# subckt_SMPS_EMI_filter.net
KiCad netlist of a schematic drawn in Altium Designer
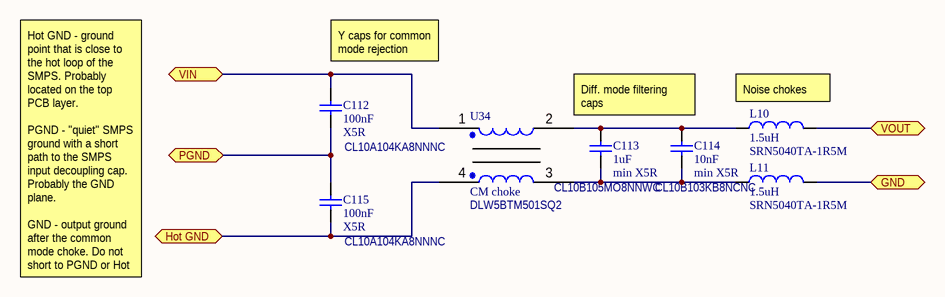
[diagram p0: subckt_SMPS_EMI_filter.SchDoc]

(export (version "E")
  (design (tool "Eeschema 10.0.6"))
  (components
    (comp (ref "C112")
      (value "100nF")
      (footprint "CAP0603")
      (description "Capacitor")
      (fields (field (name "DIELECTRIC") "X5R") (field (name "MODEL") "CL10A104KA8NNNC"))
      (libsource (lib "lib_basic") (part "Capacitor"))
    )
    (comp (ref "C113")
      (value "1uF")
      (footprint "CAP0603")
      (description "Capacitor")
      (fields (field (name "DIELECTRIC") "min X5R") (field (name "MODEL") "CL10B105MO8NNWC"))
      (libsource (lib "lib_basic") (part "Capacitor"))
    )
    (comp (ref "C114")
      (value "10nF")
      (footprint "CAP0603")
      (description "Capacitor")
      (fields (field (name "DIELECTRIC") "min X5R") (field (name "MODEL") "CL10B103KB8NCNC"))
      (libsource (lib "lib_basic") (part "Capacitor"))
    )
    (comp (ref "C115")
      (value "100nF")
      (footprint "CAP0603")
      (description "Capacitor")
      (fields (field (name "DIELECTRIC") "X5R") (field (name "MODEL") "CL10A104KA8NNNC"))
      (libsource (lib "lib_basic") (part "Capacitor"))
    )
    (comp (ref "L10")
      (value "1.5uH")
      (footprint "lib_basic:MHCC06030")
      (description "Inductor")
      (fields (field (name "MODEL") "SRN5040TA-1R5M"))
      (libsource (lib "lib_basic") (part "Inductor"))
    )
    (comp (ref "L11")
      (value "1.5uH")
      (footprint "lib_basic:MHCC06030")
      (description "Inductor")
      (fields (field (name "MODEL") "SRN5040TA-1R5M"))
      (libsource (lib "lib_basic") (part "Inductor"))
    )
    (comp (ref "U34")
      (value "CM choke")
      (footprint "lib_power:Murata_DLW5A/5B")
      (description "Common mode choke")
      (fields (field (name "MODEL") "DLW5BTM501SQ2"))
      (libsource (lib "lib_power") (part "Common_choke"))
    )
  )
  (nets
    (net (code "1") (name "/GND") (class "Default")
      (node (ref "L11") (pin "2") (pinfunction "2_2") (pintype "passive"))
    )
    (net (code "2") (name "/Hot GND") (class "Default")
      (node (ref "C115") (pin "1") (pinfunction "1_1") (pintype "passive"))
      (node (ref "U34") (pin "4") (pinfunction "4_4") (pintype "passive"))
    )
    (net (code "3") (name "/PGND") (class "Default")
      (node (ref "C112") (pin "1") (pinfunction "1_1") (pintype "passive"))
      (node (ref "C115") (pin "2") (pinfunction "2_2") (pintype "passive"))
    )
    (net (code "4") (name "/VIN") (class "Default")
      (node (ref "C112") (pin "2") (pinfunction "2_2") (pintype "passive"))
      (node (ref "U34") (pin "1") (pinfunction "1_1") (pintype "passive"))
    )
    (net (code "5") (name "/VOUT") (class "Default")
      (node (ref "L10") (pin "2") (pinfunction "2_2") (pintype "passive"))
    )
    (net (code "6") (name "Net-(C113-Pad1)") (class "Default")
      (node (ref "C113") (pin "1") (pinfunction "1_1") (pintype "passive"))
      (node (ref "C114") (pin "1") (pinfunction "1_1") (pintype "passive"))
      (node (ref "L11") (pin "1") (pinfunction "1_1") (pintype "passive"))
      (node (ref "U34") (pin "3") (pinfunction "3_3") (pintype "passive"))
    )
    (net (code "7") (name "Net-(C113-Pad2)") (class "Default")
      (node (ref "C113") (pin "2") (pinfunction "2_2") (pintype "passive"))
      (node (ref "C114") (pin "2") (pinfunction "2_2") (pintype "passive"))
      (node (ref "L10") (pin "1") (pinfunction "1_1") (pintype "passive"))
      (node (ref "U34") (pin "2") (pinfunction "2_2") (pintype "passive"))
    )
  )
)
